# Fri3D_2026_Peripherals.net
KiCad netlist of a schematic drawn in Altium Designer
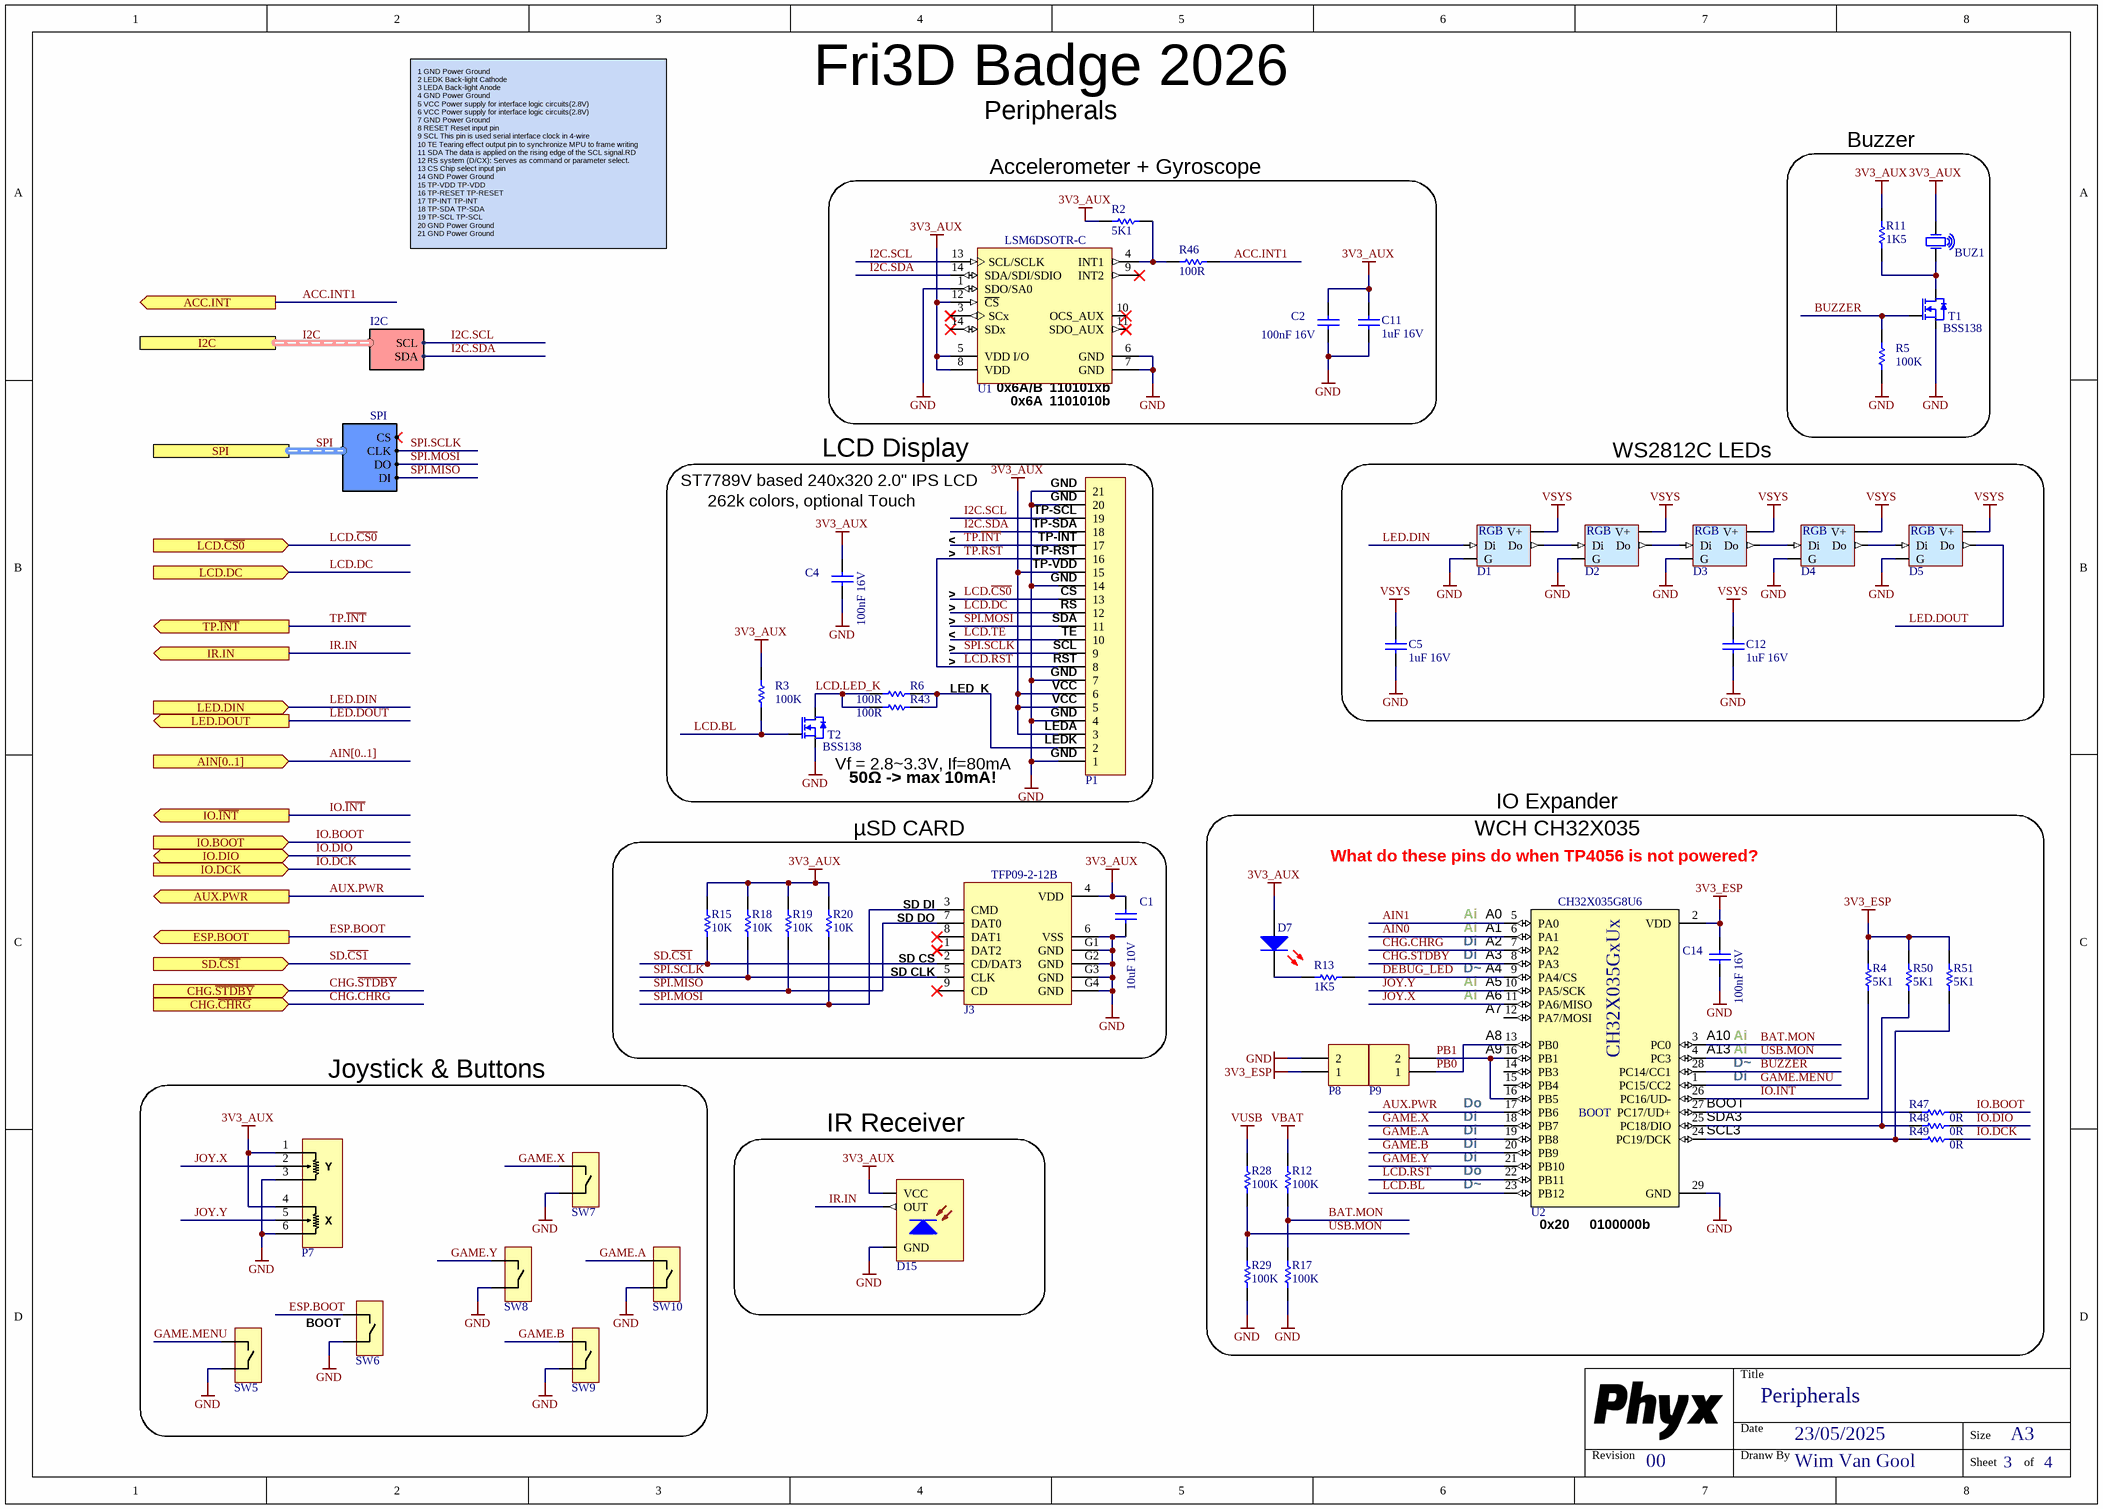
[diagram p0: Fri3D_2026_Peripherals.SchDoc]

(export (version "E")
  (design (tool "Eeschema 10.0.6"))
  (components
    (comp (ref "BUZ1")
      (value "12x12x3mm Piezo Buzzer Transducer 81dB")
      (footprint "CUI_CMT-1203-SMT")
      (description "Crystal Oscillator")
      (libsource (lib "Phyx_Components") (part "Buzzer"))
    )
    (comp (ref "C1")
      (value "10uF 10V")
      (footprint "C0805_N")
      (description "Capacitor Ceramic")
      (libsource (lib "Phyx_Components") (part "CAP_CERAMIC"))
    )
    (comp (ref "C2")
      (value "100nF 16V")
      (footprint "C0603_N")
      (description "Capacitor Ceramic")
      (libsource (lib "Phyx_Components") (part "CAP_CERAMIC"))
    )
    (comp (ref "C4")
      (value "100nF 16V")
      (footprint "C0603_N")
      (description "Capacitor Ceramic")
      (libsource (lib "Phyx_Components") (part "CAP_CERAMIC"))
    )
    (comp (ref "C5")
      (value "1uF 16V")
      (footprint "C0603_N")
      (description "Capacitor Ceramic")
      (libsource (lib "Phyx_Components") (part "CAP_CERAMIC"))
    )
    (comp (ref "C11")
      (value "1uF 16V")
      (footprint "C0603_N")
      (description "Capacitor Ceramic")
      (libsource (lib "Phyx_Components") (part "CAP_CERAMIC"))
    )
    (comp (ref "C12")
      (value "1uF 16V")
      (footprint "C0603_N")
      (description "Capacitor Ceramic")
      (libsource (lib "Phyx_Components") (part "CAP_CERAMIC"))
    )
    (comp (ref "C14")
      (value "100nF 16V")
      (footprint "C0603_N")
      (description "Capacitor Ceramic")
      (libsource (lib "Phyx_Components") (part "CAP_CERAMIC"))
    )
    (comp (ref "D1")
      (value "WS2812 based digital RGB LED 5050 White package reduced current")
      (footprint "LED_5050_WS2812B_WHITE")
      (description "=Description")
      (libsource (lib "Phyx_Components") (part "LED_RGB_WS2812B_5050"))
    )
    (comp (ref "D2")
      (value "WS2812 based digital RGB LED 5050 White package reduced current")
      (footprint "LED_5050_WS2812B_WHITE")
      (description "=Description")
      (libsource (lib "Phyx_Components") (part "LED_RGB_WS2812B_5050"))
    )
    (comp (ref "D3")
      (value "WS2812 based digital RGB LED 5050 White package reduced current")
      (footprint "LED_5050_WS2812B_WHITE")
      (description "=Description")
      (libsource (lib "Phyx_Components") (part "LED_RGB_WS2812B_5050"))
    )
    (comp (ref "D4")
      (value "WS2812 based digital RGB LED 5050 White package reduced current")
      (footprint "LED_5050_WS2812B_WHITE")
      (description "=Description")
      (libsource (lib "Phyx_Components") (part "LED_RGB_WS2812B_5050"))
    )
    (comp (ref "D5")
      (value "WS2812 based digital RGB LED 5050 White package reduced current")
      (footprint "LED_5050_WS2812B_WHITE")
      (description "=Description")
      (libsource (lib "Phyx_Components") (part "LED_RGB_WS2812B_5050"))
    )
    (comp (ref "D7")
      (value "Default 0805 Red LED")
      (footprint "LED_0805_RD")
      (description "=Description")
      (libsource (lib "Phyx_Components") (part "LED_RED"))
    )
    (comp (ref "D15")
      (value "ZIRM-5042B-42-Z2 Infrared Receiver 38 kHz 45° 2.7-5.5V 940nm")
      (footprint "CHAU_ZIRM-5042B-42-Z2")
      (description "=Description")
      (libsource (lib "Phyx_Components") (part "PHO_IR_TSOP381x"))
    )
    (comp (ref "J3")
      (value "Micro SD PiPo Push-Push")
      (footprint "TFP09-2-12B")
      (description "=Description")
      (fields (field (name "SUPPLIER PART NUMBER 1") "TFP09-2-12B"))
      (libsource (lib "Phyx_Components") (part "TFP09-2-12B"))
    )
    (comp (ref "P1")
      (value "FH35C-21S-0.3SHW Top and Bottom Contacts 0.3mm 21pin")
      (footprint "HRS_FH35C-21S-0.3SHW")
      (libsource (lib "Phyx_Components") (part "Header 21"))
    )
    (comp (ref "P7")
      (value "PSP Mini Joystick")
      (footprint "PSP_Mini_Joystick")
      (libsource (lib "Phyx_Components") (part "PSP_Mini_Joystick"))
    )
    (comp (ref "P8") (value "Header 2") (footprint "HDR1X2") (libsource (lib "") (part "Header 2_1")))
    (comp (ref "P9")
      (value "Header 2")
      (footprint "HDR1X2")
      (libsource (lib "Phyx_Components") (part "Header 2"))
    )
    (comp (ref "R2")
      (value "5K1")
      (footprint "R0603_N")
      (libsource (lib "Phyx_Components") (part "RESISTOR"))
    )
    (comp (ref "R3")
      (value "100K")
      (footprint "R0603_N")
      (libsource (lib "Phyx_Components") (part "RESISTOR"))
    )
    (comp (ref "R4")
      (value "5K1")
      (footprint "R0603_N")
      (libsource (lib "Phyx_Components") (part "RESISTOR"))
    )
    (comp (ref "R5")
      (value "100K")
      (footprint "R0603_N")
      (libsource (lib "Phyx_Components") (part "RESISTOR"))
    )
    (comp (ref "R6")
      (value "100R")
      (footprint "R0603_N")
      (libsource (lib "Phyx_Components") (part "RESISTOR"))
    )
    (comp (ref "R11")
      (value "1K5")
      (footprint "R0603_N")
      (libsource (lib "Phyx_Components") (part "RESISTOR"))
    )
    (comp (ref "R12")
      (value "100K")
      (footprint "R0603_N")
      (libsource (lib "Phyx_Components") (part "RESISTOR"))
    )
    (comp (ref "R13")
      (value "1K5")
      (footprint "R0603_N")
      (libsource (lib "Phyx_Components") (part "RESISTOR"))
    )
    (comp (ref "R15")
      (value "10K")
      (footprint "R0603_N")
      (libsource (lib "Phyx_Components") (part "RESISTOR"))
    )
    (comp (ref "R17")
      (value "100K")
      (footprint "R0603_N")
      (libsource (lib "Phyx_Components") (part "RESISTOR"))
    )
    (comp (ref "R18")
      (value "10K")
      (footprint "R0603_N")
      (libsource (lib "Phyx_Components") (part "RESISTOR"))
    )
    (comp (ref "R19")
      (value "10K")
      (footprint "R0603_N")
      (libsource (lib "Phyx_Components") (part "RESISTOR"))
    )
    (comp (ref "R20")
      (value "10K")
      (footprint "R0603_N")
      (libsource (lib "Phyx_Components") (part "RESISTOR"))
    )
    (comp (ref "R28")
      (value "100K")
      (footprint "R0603_N")
      (libsource (lib "Phyx_Components") (part "RESISTOR"))
    )
    (comp (ref "R29")
      (value "100K")
      (footprint "R0603_N")
      (libsource (lib "Phyx_Components") (part "RESISTOR"))
    )
    (comp (ref "R43")
      (value "100R")
      (footprint "R0603_N")
      (libsource (lib "Phyx_Components") (part "RESISTOR"))
    )
    (comp (ref "R46")
      (value "100R")
      (footprint "R0603_N")
      (libsource (lib "Phyx_Components") (part "RESISTOR"))
    )
    (comp (ref "R47")
      (value "0R")
      (footprint "R0603_N")
      (libsource (lib "Phyx_Components") (part "RESISTOR"))
    )
    (comp (ref "R48")
      (value "0R")
      (footprint "R0603_N")
      (libsource (lib "Phyx_Components") (part "RESISTOR"))
    )
    (comp (ref "R49")
      (value "0R")
      (footprint "R0603_N")
      (libsource (lib "Phyx_Components") (part "RESISTOR"))
    )
    (comp (ref "R50")
      (value "5K1")
      (footprint "R0603_N")
      (libsource (lib "Phyx_Components") (part "RESISTOR"))
    )
    (comp (ref "R51")
      (value "5K1")
      (footprint "R0603_N")
      (libsource (lib "Phyx_Components") (part "RESISTOR"))
    )
    (comp (ref "SW5")
      (value "SKPMAME010 6x6 TACTG Switch")
      (footprint "ALPS_SKPMAME010")
      (libsource (lib "Phyx_Components") (part "SW_TACT"))
    )
    (comp (ref "SW6")
      (value "SKPMAME010 6x6 TACTG Switch")
      (footprint "ALPS_SKPMAME010")
      (libsource (lib "Phyx_Components") (part "SW_TACT"))
    )
    (comp (ref "SW7")
      (value "SKPMAME010 6x6 TACTG Switch")
      (footprint "ALPS_SKPMAME010")
      (libsource (lib "Phyx_Components") (part "SW_TACT"))
    )
    (comp (ref "SW8")
      (value "SKPMAME010 6x6 TACTG Switch")
      (footprint "ALPS_SKPMAME010")
      (libsource (lib "Phyx_Components") (part "SW_TACT"))
    )
    (comp (ref "SW9")
      (value "SKPMAME010 6x6 TACTG Switch")
      (footprint "ALPS_SKPMAME010")
      (libsource (lib "Phyx_Components") (part "SW_TACT"))
    )
    (comp (ref "SW10")
      (value "SKPMAME010 6x6 TACTG Switch")
      (footprint "ALPS_SKPMAME010")
      (libsource (lib "Phyx_Components") (part "SW_TACT"))
    )
    (comp (ref "T1")
      (value "BSS138")
      (footprint "SOT23-3")
      (fields (field (name "Comment") "0.2A N-Ch MOSFET Vgs 3.2"))
      (libsource (lib "Phyx_Components") (part "N_MOSFET_GSD"))
    )
    (comp (ref "T2")
      (value "BSS138")
      (footprint "SOT23-3")
      (fields (field (name "Comment") "0.2A N-Ch MOSFET Vgs 3.2"))
      (libsource (lib "Phyx_Components") (part "N_MOSFET_GSD"))
    )
    (comp (ref "U1")
      (value "LSM6DSOTR-C")
      (footprint "STM_LGA14_2.5x3")
      (description "=Description")
      (fields (field (name "Comment") "Acceleration ±2, ±4, ±8, ±16g Gyro ±125, ±250, ±500, ±1000, ±2000dps"))
      (libsource (lib "Phyx_Components") (part "STM_LSM6DSO"))
    )
    (comp (ref "U2")
      (value "CH32X035G8U6")
      (footprint "QFN_28_4.0x4.0_P0.4")
      (fields
        (field (name "Comment") "WCH CH32X035G8U6 QFN28 RISC-V 32-bit MCU, 62KB Flash, 10KB RAM, USB PD")
      )
      (libsource (lib "Phyx_Components") (part "WCH_CH32X035GxUx"))
    )
  )
  (nets
    (net (code "3") (name "/ACC.INT1") (class "Default")
      (node (ref "R46") (pin "2") (pinfunction "2_2") (pintype "passive"))
    )
    (net (code "4") (name "/AIN0") (class "Default")
      (node (ref "U2") (pin "6") (pinfunction "PA1_6") (pintype "bidirectional"))
    )
    (net (code "5") (name "/AIN1") (class "Default")
      (node (ref "U2") (pin "5") (pinfunction "PA0_5") (pintype "bidirectional"))
    )
    (net (code "7") (name "/AUX.PWR") (class "Default")
      (node (ref "U2") (pin "17") (pinfunction "PB6_17") (pintype "bidirectional"))
    )
    (net (code "8") (name "/BAT.MON") (class "Default")
      (node (ref "R12") (pin "2") (pinfunction "2_2") (pintype "passive"))
      (node (ref "R17") (pin "1") (pinfunction "1_1") (pintype "passive"))
      (node (ref "U2") (pin "3") (pinfunction "PC0_3") (pintype "bidirectional"))
    )
    (net (code "9") (name "/BUZZER") (class "Default")
      (node (ref "R5") (pin "1") (pinfunction "1_1") (pintype "passive"))
      (node (ref "T1") (pin "1") (pinfunction "G_1") (pintype "passive"))
      (node (ref "U2") (pin "28") (pinfunction "PC14/CC1_28") (pintype "bidirectional"))
    )
    (net (code "10") (name "/CHG.~{CHRG}") (class "Default")
      (node (ref "U2") (pin "7") (pinfunction "PA2_7") (pintype "bidirectional"))
    )
    (net (code "11") (name "/CHG.~{STDBY}") (class "Default")
      (node (ref "U2") (pin "8") (pinfunction "PA3_8") (pintype "bidirectional"))
    )
    (net (code "12") (name "/DEBUG_LED") (class "Default")
      (node (ref "R13") (pin "2") (pinfunction "2_2") (pintype "passive"))
      (node (ref "U2") (pin "9") (pinfunction "PA4/CS_9") (pintype "bidirectional"))
    )
    (net (code "13") (name "/ESP.BOOT") (class "Default")
      (node (ref "SW6") (pin "1") (pinfunction "1_1") (pintype "passive"))
    )
    (net (code "14") (name "/GAME.A") (class "Default")
      (node (ref "SW10") (pin "1") (pinfunction "1_1") (pintype "passive"))
      (node (ref "U2") (pin "19") (pinfunction "PB8_19") (pintype "bidirectional"))
    )
    (net (code "15") (name "/GAME.B") (class "Default")
      (node (ref "SW9") (pin "1") (pinfunction "1_1") (pintype "passive"))
      (node (ref "U2") (pin "20") (pinfunction "PB9_20") (pintype "bidirectional"))
    )
    (net (code "16") (name "/GAME.MENU") (class "Default")
      (node (ref "SW5") (pin "1") (pinfunction "1_1") (pintype "passive"))
      (node (ref "U2") (pin "1") (pinfunction "PC15/CC2_1") (pintype "bidirectional"))
    )
    (net (code "17") (name "/GAME.X") (class "Default")
      (node (ref "SW7") (pin "1") (pinfunction "1_1") (pintype "passive"))
      (node (ref "U2") (pin "18") (pinfunction "PB7_18") (pintype "bidirectional"))
    )
    (net (code "18") (name "/GAME.Y") (class "Default")
      (node (ref "SW8") (pin "1") (pinfunction "1_1") (pintype "passive"))
      (node (ref "U2") (pin "21") (pinfunction "PB10_21") (pintype "bidirectional"))
    )
    (net (code "19") (name "/I2C.SCL") (class "Default")
      (node (ref "P1") (pin "19") (pinfunction "19_19") (pintype "passive"))
      (node (ref "U1") (pin "13") (pinfunction "SCL/SCLK_13") (pintype "input"))
    )
    (net (code "20") (name "/I2C.SDA") (class "Default")
      (node (ref "P1") (pin "18") (pinfunction "18_18") (pintype "passive"))
      (node (ref "U1") (pin "14") (pinfunction "SDA/SDI/SDIO_14") (pintype "bidirectional"))
    )
    (net (code "22") (name "/IO.BOOT") (class "Default")
      (node (ref "R47") (pin "2") (pinfunction "2_2") (pintype "passive"))
    )
    (net (code "23") (name "/IO.DCK") (class "Default")
      (node (ref "R49") (pin "2") (pinfunction "2_2") (pintype "passive"))
    )
    (net (code "24") (name "/IO.DIO") (class "Default")
      (node (ref "R48") (pin "2") (pinfunction "2_2") (pintype "passive"))
    )
    (net (code "25") (name "/IO.~{INT}") (class "Default")
      (node (ref "R4") (pin "2") (pinfunction "2_2") (pintype "passive"))
      (node (ref "U2") (pin "26") (pinfunction "PC16/UD-_26") (pintype "bidirectional"))
    )
    (net (code "26") (name "/IR.IN") (class "Default")
      (node (ref "D15") (pin "1") (pinfunction "OUT_1") (pintype "output"))
    )
    (net (code "27") (name "/JOY.X") (class "Default")
      (node (ref "P7") (pin "2") (pinfunction "2_2") (pintype "passive"))
      (node (ref "U2") (pin "11") (pinfunction "PA6/MISO_11") (pintype "bidirectional"))
    )
    (net (code "28") (name "/JOY.Y") (class "Default")
      (node (ref "P7") (pin "5") (pinfunction "5_5") (pintype "passive"))
      (node (ref "U2") (pin "10") (pinfunction "PA5/SCK_10") (pintype "bidirectional"))
    )
    (net (code "29") (name "/LCD.BL") (class "Default")
      (node (ref "R3") (pin "2") (pinfunction "2_2") (pintype "passive"))
      (node (ref "T2") (pin "1") (pinfunction "G_1") (pintype "passive"))
      (node (ref "U2") (pin "23") (pinfunction "PB12_23") (pintype "bidirectional"))
    )
    (net (code "30") (name "/LCD.DC") (class "Default")
      (node (ref "P1") (pin "12") (pinfunction "12_12") (pintype "passive"))
    )
    (net (code "31") (name "/LCD.LED_K") (class "Default")
      (node (ref "R43") (pin "2") (pinfunction "2_2") (pintype "passive"))
      (node (ref "R6") (pin "2") (pinfunction "2_2") (pintype "passive"))
      (node (ref "T2") (pin "3") (pinfunction "D_3") (pintype "passive"))
    )
    (net (code "32") (name "/LCD.TE") (class "Default")
      (node (ref "P1") (pin "10") (pinfunction "10_10") (pintype "passive"))
    )
    (net (code "33") (name "/LCD.~{CS0}") (class "Default")
      (node (ref "P1") (pin "13") (pinfunction "13_13") (pintype "passive"))
    )
    (net (code "34") (name "/LCD.~{RST}") (class "Default")
      (node (ref "P1") (pin "16") (pinfunction "16_16") (pintype "passive"))
      (node (ref "P1") (pin "8") (pinfunction "8_8") (pintype "passive"))
      (node (ref "U2") (pin "22") (pinfunction "PB11_22") (pintype "bidirectional"))
    )
    (net (code "35") (name "/LED.DIN") (class "Default")
      (node (ref "D1") (pin "4") (pinfunction "Di_4") (pintype "input"))
    )
    (net (code "36") (name "/LED.DOUT") (class "Default")
      (node (ref "D5") (pin "2") (pinfunction "Do_2") (pintype "output"))
    )
    (net (code "37") (name "/PB0") (class "Default")
      (node (ref "P9") (pin "1") (pinfunction "1_1") (pintype "passive"))
      (node (ref "U2") (pin "13") (pinfunction "PB0_13") (pintype "bidirectional"))
    )
    (net (code "38") (name "/PB1") (class "Default")
      (node (ref "P9") (pin "2") (pinfunction "2_2") (pintype "passive"))
      (node (ref "U2") (pin "16") (pinfunction "PB1_16") (pintype "bidirectional"))
    )
    (net (code "39") (name "/SD.~{CS1}") (class "Default")
      (node (ref "J3") (pin "2") (pinfunction "CD/DAT3_2") (pintype "passive"))
      (node (ref "R15") (pin "2") (pinfunction "2_2") (pintype "passive"))
    )
    (net (code "40") (name "/SPI.MISO") (class "Default")
      (node (ref "J3") (pin "7") (pinfunction "DAT0_7") (pintype "passive"))
      (node (ref "R19") (pin "2") (pinfunction "2_2") (pintype "passive"))
    )
    (net (code "41") (name "/SPI.MOSI") (class "Default")
      (node (ref "J3") (pin "3") (pinfunction "CMD_3") (pintype "passive"))
      (node (ref "P1") (pin "11") (pinfunction "11_11") (pintype "passive"))
      (node (ref "R20") (pin "2") (pinfunction "2_2") (pintype "passive"))
    )
    (net (code "42") (name "/SPI.SCLK") (class "Default")
      (node (ref "J3") (pin "5") (pinfunction "CLK_5") (pintype "passive"))
      (node (ref "P1") (pin "9") (pinfunction "9_9") (pintype "passive"))
      (node (ref "R18") (pin "2") (pinfunction "2_2") (pintype "passive"))
    )
    (net (code "44") (name "/TP.~{INT}") (class "Default")
      (node (ref "P1") (pin "17") (pinfunction "17_17") (pintype "passive"))
    )
    (net (code "45") (name "/USB.MON") (class "Default")
      (node (ref "R28") (pin "2") (pinfunction "2_2") (pintype "passive"))
      (node (ref "R29") (pin "1") (pinfunction "1_1") (pintype "passive"))
      (node (ref "U2") (pin "4") (pinfunction "PC3_4") (pintype "bidirectional"))
    )
    (net (code "46") (name "3V3_AUX") (class "Default")
      (node (ref "BUZ1") (pin "2") (pinfunction "OSC2_2") (pintype "passive"))
      (node (ref "C1") (pin "1") (pinfunction "1_1") (pintype "passive"))
      (node (ref "C11") (pin "1") (pinfunction "1_1") (pintype "passive"))
      (node (ref "C2") (pin "1") (pinfunction "1_1") (pintype "passive"))
      (node (ref "C4") (pin "1") (pinfunction "1_1") (pintype "passive"))
      (node (ref "D15") (pin "3") (pinfunction "VCC_3") (pintype "power_in"))
      (node (ref "D7") (pin "1") (pinfunction "A_1") (pintype "passive"))
      (node (ref "J3") (pin "4") (pinfunction "VDD_4") (pintype "power_in"))
      (node (ref "P1") (pin "15") (pinfunction "15_15") (pintype "passive"))
      (node (ref "P1") (pin "3") (pinfunction "3_3") (pintype "passive"))
      (node (ref "P1") (pin "5") (pinfunction "5_5") (pintype "passive"))
      (node (ref "P1") (pin "6") (pinfunction "6_6") (pintype "passive"))
      (node (ref "P7") (pin "1") (pinfunction "1_1") (pintype "passive"))
      (node (ref "P7") (pin "4") (pinfunction "4_4") (pintype "passive"))
      (node (ref "R11") (pin "2") (pinfunction "2_2") (pintype "passive"))
      (node (ref "R15") (pin "1") (pinfunction "1_1") (pintype "passive"))
      (node (ref "R18") (pin "1") (pinfunction "1_1") (pintype "passive"))
      (node (ref "R19") (pin "1") (pinfunction "1_1") (pintype "passive"))
      (node (ref "R2") (pin "1") (pinfunction "1_1") (pintype "passive"))
      (node (ref "R20") (pin "1") (pinfunction "1_1") (pintype "passive"))
      (node (ref "R3") (pin "1") (pinfunction "1_1") (pintype "passive"))
      (node (ref "U1") (pin "12") (pinfunction "~{CS}_12") (pintype "input"))
      (node (ref "U1") (pin "5") (pinfunction "VDD_I/O_5") (pintype "power_in"))
      (node (ref "U1") (pin "8") (pinfunction "VDD_8") (pintype "power_in"))
    )
    (net (code "47") (name "3V3_ESP") (class "Default")
      (node (ref "C14") (pin "1") (pinfunction "1_1") (pintype "passive"))
      (node (ref "P8") (pin "1") (pinfunction "1_1") (pintype "passive"))
      (node (ref "R4") (pin "1") (pinfunction "1_1") (pintype "passive"))
      (node (ref "R50") (pin "1") (pinfunction "1_1") (pintype "passive"))
      (node (ref "R51") (pin "1") (pinfunction "1_1") (pintype "passive"))
      (node (ref "U2") (pin "2") (pinfunction "VDD_2") (pintype "power_in"))
    )
    (net (code "48") (name "GND") (class "Default")
      (node (ref "C1") (pin "2") (pinfunction "2_2") (pintype "passive"))
      (node (ref "C11") (pin "2") (pinfunction "2_2") (pintype "passive"))
      (node (ref "C12") (pin "2") (pinfunction "2_2") (pintype "passive"))
      (node (ref "C14") (pin "2") (pinfunction "2_2") (pintype "passive"))
      (node (ref "C2") (pin "2") (pinfunction "2_2") (pintype "passive"))
      (node (ref "C4") (pin "2") (pinfunction "2_2") (pintype "passive"))
      (node (ref "C5") (pin "2") (pinfunction "2_2") (pintype "passive"))
      (node (ref "D1") (pin "3") (pinfunction "G_3") (pintype "power_in"))
      (node (ref "D15") (pin "2") (pinfunction "GND_2") (pintype "power_in"))
      (node (ref "D2") (pin "3") (pinfunction "G_3") (pintype "power_in"))
      (node (ref "D3") (pin "3") (pinfunction "G_3") (pintype "power_in"))
      (node (ref "D4") (pin "3") (pinfunction "G_3") (pintype "power_in"))
      (node (ref "D5") (pin "3") (pinfunction "G_3") (pintype "power_in"))
      (node (ref "J3") (pin "6") (pinfunction "VSS_6") (pintype "power_in"))
      (node (ref "J3") (pin "G1") (pinfunction "GND_G1") (pintype "power_in"))
      (node (ref "J3") (pin "G2") (pinfunction "GND_G2") (pintype "power_in"))
      (node (ref "J3") (pin "G3") (pinfunction "GND_G3") (pintype "power_in"))
      (node (ref "J3") (pin "G4") (pinfunction "GND_G4") (pintype "power_in"))
      (node (ref "P1") (pin "1") (pinfunction "1_1") (pintype "passive"))
      (node (ref "P1") (pin "14") (pinfunction "14_14") (pintype "passive"))
      (node (ref "P1") (pin "20") (pinfunction "20_20") (pintype "passive"))
      (node (ref "P1") (pin "21") (pinfunction "21_21") (pintype "passive"))
      (node (ref "P1") (pin "4") (pinfunction "4_4") (pintype "passive"))
      (node (ref "P1") (pin "7") (pinfunction "7_7") (pintype "passive"))
      (node (ref "P7") (pin "3") (pinfunction "3_3") (pintype "passive"))
      (node (ref "P7") (pin "6") (pinfunction "6_6") (pintype "passive"))
      (node (ref "P8") (pin "2") (pinfunction "2_2") (pintype "passive"))
      (node (ref "R17") (pin "2") (pinfunction "2_2") (pintype "passive"))
      (node (ref "R29") (pin "2") (pinfunction "2_2") (pintype "passive"))
      (node (ref "R5") (pin "2") (pinfunction "2_2") (pintype "passive"))
      (node (ref "SW10") (pin "2") (pinfunction "2_2") (pintype "passive"))
      (node (ref "SW5") (pin "2") (pinfunction "2_2") (pintype "passive"))
      (node (ref "SW6") (pin "2") (pinfunction "2_2") (pintype "passive"))
      (node (ref "SW7") (pin "2") (pinfunction "2_2") (pintype "passive"))
      (node (ref "SW8") (pin "2") (pinfunction "2_2") (pintype "passive"))
      (node (ref "SW9") (pin "2") (pinfunction "2_2") (pintype "passive"))
      (node (ref "T1") (pin "2") (pinfunction "S_2") (pintype "passive"))
      (node (ref "T2") (pin "2") (pinfunction "S_2") (pintype "passive"))
      (node (ref "U1") (pin "1") (pinfunction "SDO/SA0_1") (pintype "bidirectional"))
      (node (ref "U1") (pin "6") (pinfunction "GND_6") (pintype "power_in"))
      (node (ref "U1") (pin "7") (pinfunction "GND_7") (pintype "power_in"))
      (node (ref "U2") (pin "29") (pinfunction "GND_29") (pintype "power_in"))
    )
    (net (code "49") (name "Net-(BUZ1-OSC1)") (class "Default")
      (node (ref "BUZ1") (pin "1") (pinfunction "OSC1_1") (pintype "passive"))
      (node (ref "R11") (pin "1") (pinfunction "1_1") (pintype "passive"))
      (node (ref "T1") (pin "3") (pinfunction "D_3") (pintype "passive"))
    )
    (net (code "50") (name "Net-(D1-Do)") (class "Default")
      (node (ref "D1") (pin "2") (pinfunction "Do_2") (pintype "output"))
      (node (ref "D2") (pin "4") (pinfunction "Di_4") (pintype "input"))
    )
    (net (code "51") (name "Net-(D2-Do)") (class "Default")
      (node (ref "D2") (pin "2") (pinfunction "Do_2") (pintype "output"))
      (node (ref "D3") (pin "4") (pinfunction "Di_4") (pintype "input"))
    )
    (net (code "52") (name "Net-(D3-Do)") (class "Default")
      (node (ref "D3") (pin "2") (pinfunction "Do_2") (pintype "output"))
      (node (ref "D4") (pin "4") (pinfunction "Di_4") (pintype "input"))
    )
    (net (code "53") (name "Net-(D4-Do)") (class "Default")
      (node (ref "D4") (pin "2") (pinfunction "Do_2") (pintype "output"))
      (node (ref "D5") (pin "4") (pinfunction "Di_4") (pintype "input"))
    )
    (net (code "54") (name "Net-(D7-K)") (class "Default")
      (node (ref "D7") (pin "2") (pinfunction "K_2") (pintype "passive"))
      (node (ref "R13") (pin "1") (pinfunction "1_1") (pintype "passive"))
    )
    (net (code "55") (name "Net-(P1-Pad2)") (class "Default")
      (node (ref "P1") (pin "2") (pinfunction "2_2") (pintype "passive"))
      (node (ref "R43") (pin "1") (pinfunction "1_1") (pintype "passive"))
      (node (ref "R6") (pin "1") (pinfunction "1_1") (pintype "passive"))
    )
    (net (code "56") (name "Net-(U1-INT1)") (class "Default")
      (node (ref "R2") (pin "2") (pinfunction "2_2") (pintype "passive"))
      (node (ref "R46") (pin "1") (pinfunction "1_1") (pintype "passive"))
      (node (ref "U1") (pin "4") (pinfunction "INT1_4") (pintype "output"))
    )
    (net (code "57") (name "Net-(U2-PC17{slash}UD+)") (class "Default")
      (node (ref "R47") (pin "1") (pinfunction "1_1") (pintype "passive"))
      (node (ref "U2") (pin "27") (pinfunction "PC17/UD+_27") (pintype "bidirectional"))
    )
    (net (code "58") (name "Net-(U2-PC18{slash}DIO)") (class "Default")
      (node (ref "R48") (pin "1") (pinfunction "1_1") (pintype "passive"))
      (node (ref "R50") (pin "2") (pinfunction "2_2") (pintype "passive"))
      (node (ref "U2") (pin "25") (pinfunction "PC18/DIO_25") (pintype "bidirectional"))
    )
    (net (code "59") (name "Net-(U2-PC19{slash}DCK)") (class "Default")
      (node (ref "R49") (pin "1") (pinfunction "1_1") (pintype "passive"))
      (node (ref "R51") (pin "2") (pinfunction "2_2") (pintype "passive"))
      (node (ref "U2") (pin "24") (pinfunction "PC19/DCK_24") (pintype "bidirectional"))
    )
    (net (code "60") (name "VBAT") (class "Default")
      (node (ref "R12") (pin "1") (pinfunction "1_1") (pintype "passive"))
    )
    (net (code "61") (name "VSYS") (class "Default")
      (node (ref "C12") (pin "1") (pinfunction "1_1") (pintype "passive"))
      (node (ref "C5") (pin "1") (pinfunction "1_1") (pintype "passive"))
      (node (ref "D1") (pin "1") (pinfunction "V+_1") (pintype "power_in"))
      (node (ref "D2") (pin "1") (pinfunction "V+_1") (pintype "power_in"))
      (node (ref "D3") (pin "1") (pinfunction "V+_1") (pintype "power_in"))
      (node (ref "D4") (pin "1") (pinfunction "V+_1") (pintype "power_in"))
      (node (ref "D5") (pin "1") (pinfunction "V+_1") (pintype "power_in"))
    )
    (net (code "62") (name "VUSB") (class "Default")
      (node (ref "R28") (pin "1") (pinfunction "1_1") (pintype "passive"))
    )
    (net (code "63") (name "unconnected-(J3-CD-Pad9)") (class "Default")
      (node (ref "J3") (pin "9") (pinfunction "CD_9") (pintype "passive+no_connect"))
    )
    (net (code "64") (name "unconnected-(J3-DAT1-Pad8)") (class "Default")
      (node (ref "J3") (pin "8") (pinfunction "DAT1_8") (pintype "passive+no_connect"))
    )
    (net (code "65") (name "unconnected-(J3-DAT2-Pad1)") (class "Default")
      (node (ref "J3") (pin "1") (pinfunction "DAT2_1") (pintype "passive+no_connect"))
    )
    (net (code "66") (name "unconnected-(U1-INT2-Pad9)") (class "Default")
      (node (ref "U1") (pin "9") (pinfunction "INT2_9") (pintype "output+no_connect"))
    )
    (net (code "67") (name "unconnected-(U1-OCS_AUX-Pad10)") (class "Default")
      (node (ref "U1") (pin "10") (pinfunction "OCS_AUX_10") (pintype "passive+no_connect"))
    )
    (net (code "68") (name "unconnected-(U1-SCx-Pad3)") (class "Default")
      (node (ref "U1") (pin "3") (pinfunction "SCx_3") (pintype "output+no_connect"))
    )
    (net (code "69") (name "unconnected-(U1-SDO_AUX-Pad11)") (class "Default")
      (node (ref "U1") (pin "11") (pinfunction "SDO_AUX_11") (pintype "output+no_connect"))
    )
    (net (code "70") (name "unconnected-(U1-SDx-Pad14)") (class "Default")
      (node (ref "U1") (pin "14") (pinfunction "SDx_14") (pintype "bidirectional+no_connect"))
    )
    (net (code "71") (name "unconnected-(U2-PA7{slash}MOSI-Pad12)") (class "Default")
      (node (ref "U2") (pin "12") (pinfunction "PA7/MOSI_12") (pintype "bidirectional"))
    )
    (net (code "72") (name "unconnected-(U2-PB3-Pad14)") (class "Default")
      (node (ref "U2") (pin "14") (pinfunction "PB3_14") (pintype "bidirectional"))
    )
    (net (code "73") (name "unconnected-(U2-PB4-Pad15)") (class "Default")
      (node (ref "U2") (pin "15") (pinfunction "PB4_15") (pintype "bidirectional"))
    )
  )
)
